# Sheet1.net
KiCad netlist of a schematic drawn in Altium Designer
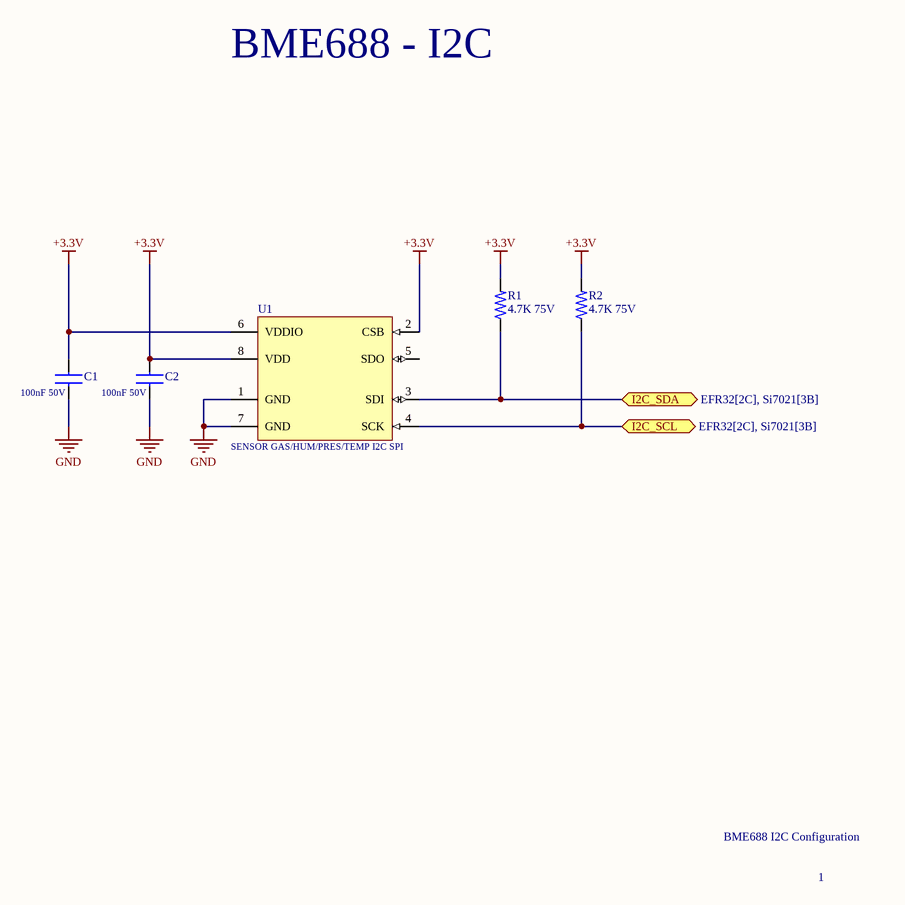
[diagram p0: Sheet1.SchDoc]

(export (version "E")
  (design (tool "Eeschema 10.0.6"))
  (components
    (comp (ref "C1")
      (value "100nF 50V")
      (footprint "CAP_0603_1MM")
      (fields
        (field (name "MANUFACTURER") "Yageo")
        (field (name "MANUFACTURER PART NUMBER") "CC0603ZRY5V9BB104")
      )
      (libsource (lib "LPEDT_project_library") (part "CC0603ZRY5V9BB104"))
    )
    (comp (ref "C2")
      (value "100nF 50V")
      (footprint "CAP_0603_1MM")
      (fields
        (field (name "MANUFACTURER") "Yageo")
        (field (name "MANUFACTURER PART NUMBER") "CC0603ZRY5V9BB104")
      )
      (libsource (lib "LPEDT_project_library") (part "CC0603ZRY5V9BB104"))
    )
    (comp (ref "R1")
      (value "4.7K 75V")
      (footprint "RES_0603_1608X06")
      (fields
        (field (name "MANUFACTURER") "Stackpole Electronics")
        (field (name "MANUFACTURER PART NUMBER") "RMCF0603FT4K70")
        (field (name "TOLERANCE") "1%")
      )
      (libsource (lib "LPEDT_project_library") (part "RMCF0603FT4K70"))
    )
    (comp (ref "R2")
      (value "4.7K 75V")
      (footprint "RES_0603_1608X06")
      (fields
        (field (name "MANUFACTURER") "Stackpole Electronics")
        (field (name "MANUFACTURER PART NUMBER") "RMCF0603FT4K70")
        (field (name "TOLERANCE") "1%")
      )
      (libsource (lib "LPEDT_project_library") (part "RMCF0603FT4K70"))
    )
    (comp (ref "U1")
      (value "SENSOR GAS/HUM/PRES/TEMP I2C SPI")
      (footprint "LGA_8_300X300X100")
      (description "Gas, Pressure, Temperature and Humidity Sensor Digital Output 1.8V 8-Pin LGA Reel")
      (fields (field (name "MANUFACTURER") "Bosch Tools") (field (name "MANUFACTURER PART NUMBER") "BME688"))
      (libsource (lib "LPEDT_project_library") (part "BME688"))
    )
  )
  (nets
    (net (code "1") (name "+3.3V") (class "Default")
      (node (ref "C1") (pin "1") (pinfunction "1_1") (pintype "passive"))
      (node (ref "C2") (pin "1") (pinfunction "1_1") (pintype "passive"))
      (node (ref "R1") (pin "2") (pinfunction "2_2") (pintype "passive"))
      (node (ref "R2") (pin "2") (pinfunction "2_2") (pintype "passive"))
      (node (ref "U1") (pin "2") (pinfunction "CSB_2") (pintype "input"))
      (node (ref "U1") (pin "6") (pinfunction "VDDIO_6") (pintype "power_in"))
      (node (ref "U1") (pin "8") (pinfunction "VDD_8") (pintype "power_in"))
    )
    (net (code "2") (name "/I2C_SCL") (class "Default")
      (node (ref "R2") (pin "1") (pinfunction "1_1") (pintype "passive"))
      (node (ref "U1") (pin "4") (pinfunction "SCK_4") (pintype "input"))
    )
    (net (code "3") (name "/I2C_SDA") (class "Default")
      (node (ref "R1") (pin "1") (pinfunction "1_1") (pintype "passive"))
      (node (ref "U1") (pin "3") (pinfunction "SDI_3") (pintype "bidirectional"))
    )
    (net (code "4") (name "GND") (class "Default")
      (node (ref "C1") (pin "2") (pinfunction "2_2") (pintype "passive"))
      (node (ref "C2") (pin "2") (pinfunction "2_2") (pintype "passive"))
      (node (ref "U1") (pin "1") (pinfunction "GND_1") (pintype "power_in"))
      (node (ref "U1") (pin "7") (pinfunction "GND_7") (pintype "power_in"))
    )
    (net (code "5") (name "unconnected-(U1-SDO-Pad5)") (class "Default")
      (node (ref "U1") (pin "5") (pinfunction "SDO_5") (pintype "bidirectional"))
    )
  )
)
